# POIstick.net
KiCad netlist of a schematic drawn in EAGLE
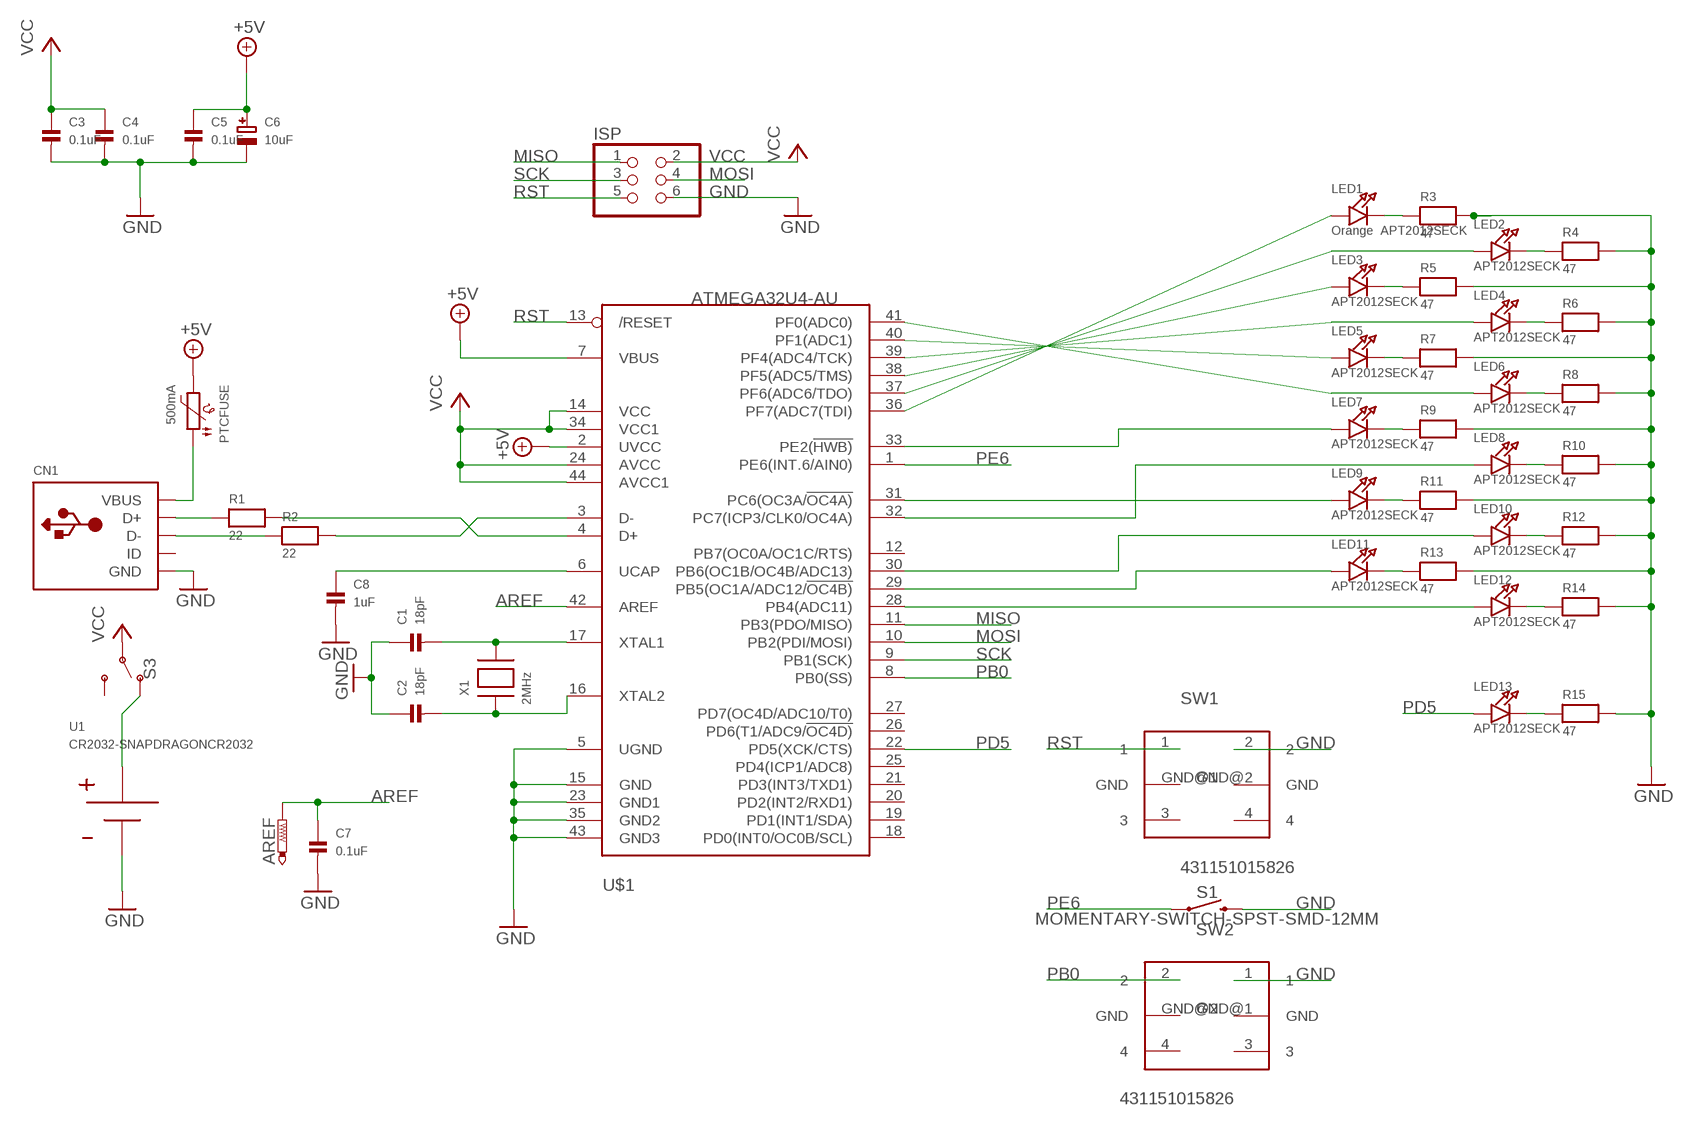
[diagram p0: schematic, sheet 1]

(export (version "E")
  (design (tool "Eeschema 10.0.6"))
  (components
    (comp (ref "AREF")
      (value "PTR1B1,27")
      (footprint "eagle-import:B1,27")
      (libsource (lib "eagle-import") (part "PTR1B1,27"))
    )
    (comp (ref "C1")
      (value "18pF")
      (footprint "eagle-import:0805")
      (libsource (lib "eagle-import") (part "CAP_CERAMIC0805"))
    )
    (comp (ref "C2")
      (value "18pF")
      (footprint "eagle-import:0805")
      (libsource (lib "eagle-import") (part "CAP_CERAMIC0805"))
    )
    (comp (ref "C3")
      (value "0.1uF")
      (footprint "eagle-import:0805")
      (libsource (lib "eagle-import") (part "CAP_CERAMIC0805"))
    )
    (comp (ref "C4")
      (value "0.1uF")
      (footprint "eagle-import:0805")
      (libsource (lib "eagle-import") (part "CAP_CERAMIC0805"))
    )
    (comp (ref "C5")
      (value "0.1uF")
      (footprint "eagle-import:0805")
      (libsource (lib "eagle-import") (part "CAP_CERAMIC0805"))
    )
    (comp (ref "C6")
      (value "10uF")
      (footprint "eagle-import:EIA3216-18_A-W")
      (libsource (lib "eagle-import") (part "CAP_TANTALUMA/3216_WAVE"))
    )
    (comp (ref "C7")
      (value "0.1uF")
      (footprint "eagle-import:0805")
      (libsource (lib "eagle-import") (part "CAP_CERAMIC0805"))
    )
    (comp (ref "C8")
      (value "1uF")
      (footprint "eagle-import:0805")
      (libsource (lib "eagle-import") (part "CAP_CERAMIC0805"))
    )
    (comp (ref "CN1")
      (value "USBMINIB")
      (footprint "eagle-import:USB-MINIB")
      (libsource (lib "eagle-import") (part "USBMINIB"))
    )
    (comp (ref "ISP")
      (value "PINHD-2X3")
      (footprint "eagle-import:2X03")
      (libsource (lib "eagle-import") (part "PINHD-2X3"))
    )
    (comp (ref "LED1")
      (value "Orange APT2012SECK")
      (footprint "eagle-import:CHIPLED_0805")
      (libsource (lib "eagle-import") (part "LED0805"))
    )
    (comp (ref "LED2")
      (value "APT2012SECK")
      (footprint "eagle-import:CHIPLED_0805")
      (libsource (lib "eagle-import") (part "LED0805"))
    )
    (comp (ref "LED3")
      (value "APT2012SECK")
      (footprint "eagle-import:CHIPLED_0805")
      (libsource (lib "eagle-import") (part "LED0805"))
    )
    (comp (ref "LED4")
      (value "APT2012SECK")
      (footprint "eagle-import:CHIPLED_0805")
      (libsource (lib "eagle-import") (part "LED0805"))
    )
    (comp (ref "LED5")
      (value "APT2012SECK")
      (footprint "eagle-import:CHIPLED_0805")
      (libsource (lib "eagle-import") (part "LED0805"))
    )
    (comp (ref "LED6")
      (value "APT2012SECK")
      (footprint "eagle-import:CHIPLED_0805")
      (libsource (lib "eagle-import") (part "LED0805"))
    )
    (comp (ref "LED7")
      (value "APT2012SECK")
      (footprint "eagle-import:CHIPLED_0805")
      (libsource (lib "eagle-import") (part "LED0805"))
    )
    (comp (ref "LED8")
      (value "APT2012SECK")
      (footprint "eagle-import:CHIPLED_0805")
      (libsource (lib "eagle-import") (part "LED0805"))
    )
    (comp (ref "LED9")
      (value "APT2012SECK")
      (footprint "eagle-import:CHIPLED_0805")
      (libsource (lib "eagle-import") (part "LED0805"))
    )
    (comp (ref "LED10")
      (value "APT2012SECK")
      (footprint "eagle-import:CHIPLED_0805")
      (libsource (lib "eagle-import") (part "LED0805"))
    )
    (comp (ref "LED11")
      (value "APT2012SECK")
      (footprint "eagle-import:CHIPLED_0805")
      (libsource (lib "eagle-import") (part "LED0805"))
    )
    (comp (ref "LED12")
      (value "APT2012SECK")
      (footprint "eagle-import:CHIPLED_0805")
      (libsource (lib "eagle-import") (part "LED0805"))
    )
    (comp (ref "LED13")
      (value "APT2012SECK")
      (footprint "eagle-import:CHIPLED_0805")
      (libsource (lib "eagle-import") (part "LED0805"))
    )
    (comp (ref "PTCFUSE")
      (value "500mA")
      (footprint "eagle-import:1206")
      (libsource (lib "eagle-import") (part "PTC1206"))
    )
    (comp (ref "R1")
      (value "22")
      (footprint "eagle-import:0805")
      (libsource (lib "eagle-import") (part "RESISTOR0805"))
    )
    (comp (ref "R2")
      (value "22")
      (footprint "eagle-import:0805")
      (libsource (lib "eagle-import") (part "RESISTOR0805"))
    )
    (comp (ref "R3")
      (value "47")
      (footprint "eagle-import:0805")
      (libsource (lib "eagle-import") (part "RESISTOR0805"))
    )
    (comp (ref "R4")
      (value "47")
      (footprint "eagle-import:0805")
      (libsource (lib "eagle-import") (part "RESISTOR0805"))
    )
    (comp (ref "R5")
      (value "47")
      (footprint "eagle-import:0805")
      (libsource (lib "eagle-import") (part "RESISTOR0805"))
    )
    (comp (ref "R6")
      (value "47")
      (footprint "eagle-import:0805")
      (libsource (lib "eagle-import") (part "RESISTOR0805"))
    )
    (comp (ref "R7")
      (value "47")
      (footprint "eagle-import:0805")
      (libsource (lib "eagle-import") (part "RESISTOR0805"))
    )
    (comp (ref "R8")
      (value "47")
      (footprint "eagle-import:0805")
      (libsource (lib "eagle-import") (part "RESISTOR0805"))
    )
    (comp (ref "R9")
      (value "47")
      (footprint "eagle-import:0805")
      (libsource (lib "eagle-import") (part "RESISTOR0805"))
    )
    (comp (ref "R10")
      (value "47")
      (footprint "eagle-import:0805")
      (libsource (lib "eagle-import") (part "RESISTOR0805"))
    )
    (comp (ref "R11")
      (value "47")
      (footprint "eagle-import:0805")
      (libsource (lib "eagle-import") (part "RESISTOR0805"))
    )
    (comp (ref "R12")
      (value "47")
      (footprint "eagle-import:0805")
      (libsource (lib "eagle-import") (part "RESISTOR0805"))
    )
    (comp (ref "R13")
      (value "47")
      (footprint "eagle-import:0805")
      (libsource (lib "eagle-import") (part "RESISTOR0805"))
    )
    (comp (ref "R14")
      (value "47")
      (footprint "eagle-import:0805")
      (libsource (lib "eagle-import") (part "RESISTOR0805"))
    )
    (comp (ref "R15")
      (value "47")
      (footprint "eagle-import:0805")
      (libsource (lib "eagle-import") (part "RESISTOR0805"))
    )
    (comp (ref "S1")
      (value "MOMENTARY-SWITCH-SPST-SMD-12MM")
      (footprint "eagle-import:TACTILE_SWITCH_SMD_12MM")
      (libsource (lib "eagle-import") (part "MOMENTARY-SWITCH-SPST-SMD-12MM"))
    )
    (comp (ref "S3")
      (value "SWITCH-SPDT-SMD-RIGHT-ANGLE")
      (footprint "eagle-import:SWITCH_SPST_SMD_A")
      (libsource (lib "eagle-import") (part "SWITCH-SPDT-SMD-RIGHT-ANGLE"))
    )
    (comp (ref "SW1")
      (value "431151015826")
      (footprint "eagle-import:431181015816")
      (libsource (lib "eagle-import") (part "431151015826"))
    )
    (comp (ref "SW2")
      (value "431151015826")
      (footprint "eagle-import:431181015816")
      (libsource (lib "eagle-import") (part "431151015826"))
    )
    (comp (ref "U$1")
      (value "ATMEGA32U4-AU")
      (footprint "eagle-import:TQFP44")
      (libsource (lib "eagle-import") (part "ATMEGA32U4-AU"))
    )
    (comp (ref "U1")
      (value "CR2032-SNAPDRAGONCR2032")
      (footprint "eagle-import:CR2032-SNAPDRAGON")
      (libsource (lib "eagle-import") (part "CR2032-SNAPDRAGONCR2032"))
    )
    (comp (ref "X1")
      (value "2MHz")
      (footprint "eagle-import:NX5032")
      (libsource (lib "eagle-import") (part "XTALNX5032"))
    )
  )
  (nets
    (net (code "1") (name "+5V") (class "Default")
      (node (ref "C5") (pin "1") (pinfunction "P$1_1") (pintype "passive"))
      (node (ref "C6") (pin "+") (pinfunction "+_+") (pintype "passive"))
      (node (ref "PTCFUSE") (pin "2") (pinfunction "2_2") (pintype "passive"))
      (node (ref "U$1") (pin "2") (pinfunction "UVCC_2") (pintype "bidirectional"))
      (node (ref "U$1") (pin "7") (pinfunction "VBUS_7") (pintype "bidirectional"))
    )
    (net (code "2") (name "/AREF") (class "Default")
      (node (ref "AREF") (pin "TP") (pinfunction "TP_TP") (pintype "input"))
      (node (ref "C7") (pin "1") (pinfunction "P$1_1") (pintype "passive"))
      (node (ref "U$1") (pin "42") (pinfunction "AREF_42") (pintype "bidirectional"))
    )
    (net (code "3") (name "/MISO") (class "Default")
      (node (ref "ISP") (pin "1") (pinfunction "1_1") (pintype "passive"))
      (node (ref "U$1") (pin "11") (pinfunction "PB3(PDO/MISO)_11") (pintype "bidirectional"))
    )
    (net (code "4") (name "/MOSI") (class "Default")
      (node (ref "ISP") (pin "4") (pinfunction "4_4") (pintype "passive"))
      (node (ref "U$1") (pin "10") (pinfunction "PB2(PDI/MOSI)_10") (pintype "bidirectional"))
    )
    (net (code "5") (name "/PB0") (class "Default")
      (node (ref "SW2") (pin "2") (pinfunction "2_2") (pintype "bidirectional"))
      (node (ref "U$1") (pin "8") (pinfunction "PB0(SS)_8") (pintype "bidirectional"))
    )
    (net (code "6") (name "/PD5") (class "Default")
      (node (ref "LED13") (pin "A") (pinfunction "A_A") (pintype "passive"))
      (node (ref "U$1") (pin "22") (pinfunction "PD5(XCK/CTS)_22") (pintype "bidirectional"))
    )
    (net (code "7") (name "/PE6") (class "Default")
      (node (ref "S1") (pin "1") (pinfunction "1_1") (pintype "passive"))
      (node (ref "U$1") (pin "1") (pinfunction "PE6(INT.6/AIN0)_1") (pintype "bidirectional"))
    )
    (net (code "8") (name "/RST") (class "Default")
      (node (ref "ISP") (pin "5") (pinfunction "5_5") (pintype "passive"))
      (node (ref "SW1") (pin "1") (pinfunction "1_1") (pintype "bidirectional"))
      (node (ref "U$1") (pin "13") (pinfunction "/RESET_13") (pintype "bidirectional"))
    )
    (net (code "9") (name "/SCK") (class "Default")
      (node (ref "ISP") (pin "3") (pinfunction "3_3") (pintype "passive"))
      (node (ref "U$1") (pin "9") (pinfunction "PB1(SCK)_9") (pintype "bidirectional"))
    )
    (net (code "10") (name "GND") (class "Default")
      (node (ref "C1") (pin "1") (pinfunction "P$1_1") (pintype "passive"))
      (node (ref "C2") (pin "1") (pinfunction "P$1_1") (pintype "passive"))
      (node (ref "C3") (pin "2") (pinfunction "P$2_2") (pintype "passive"))
      (node (ref "C4") (pin "2") (pinfunction "P$2_2") (pintype "passive"))
      (node (ref "C5") (pin "2") (pinfunction "P$2_2") (pintype "passive"))
      (node (ref "C6") (pin "-") (pinfunction "-_-") (pintype "passive"))
      (node (ref "C7") (pin "2") (pinfunction "P$2_2") (pintype "passive"))
      (node (ref "C8") (pin "2") (pinfunction "P$2_2") (pintype "passive"))
      (node (ref "CN1") (pin "GND") (pinfunction "GND_GND") (pintype "power_in"))
      (node (ref "ISP") (pin "6") (pinfunction "6_6") (pintype "passive"))
      (node (ref "R10") (pin "2") (pinfunction "2_2") (pintype "passive"))
      (node (ref "R11") (pin "2") (pinfunction "2_2") (pintype "passive"))
      (node (ref "R12") (pin "2") (pinfunction "2_2") (pintype "passive"))
      (node (ref "R13") (pin "2") (pinfunction "2_2") (pintype "passive"))
      (node (ref "R14") (pin "2") (pinfunction "2_2") (pintype "passive"))
      (node (ref "R15") (pin "2") (pinfunction "2_2") (pintype "passive"))
      (node (ref "R3") (pin "2") (pinfunction "2_2") (pintype "passive"))
      (node (ref "R4") (pin "2") (pinfunction "2_2") (pintype "passive"))
      (node (ref "R5") (pin "2") (pinfunction "2_2") (pintype "passive"))
      (node (ref "R6") (pin "2") (pinfunction "2_2") (pintype "passive"))
      (node (ref "R7") (pin "2") (pinfunction "2_2") (pintype "passive"))
      (node (ref "R8") (pin "2") (pinfunction "2_2") (pintype "passive"))
      (node (ref "R9") (pin "2") (pinfunction "2_2") (pintype "passive"))
      (node (ref "S1") (pin "3") (pinfunction "2_3") (pintype "passive"))
      (node (ref "SW1") (pin "2") (pinfunction "2_2") (pintype "bidirectional"))
      (node (ref "SW2") (pin "1") (pinfunction "1_1") (pintype "bidirectional"))
      (node (ref "U$1") (pin "15") (pinfunction "GND_15") (pintype "bidirectional"))
      (node (ref "U$1") (pin "23") (pinfunction "GND1_23") (pintype "bidirectional"))
      (node (ref "U$1") (pin "35") (pinfunction "GND2_35") (pintype "bidirectional"))
      (node (ref "U$1") (pin "43") (pinfunction "GND3_43") (pintype "bidirectional"))
      (node (ref "U$1") (pin "5") (pinfunction "UGND_5") (pintype "bidirectional"))
      (node (ref "U1") (pin "V-") (pinfunction "V-_V-") (pintype "bidirectional"))
    )
    (net (code "11") (name "Net-(C1-P$2)") (class "Default")
      (node (ref "C1") (pin "2") (pinfunction "P$2_2") (pintype "passive"))
      (node (ref "U$1") (pin "17") (pinfunction "XTAL1_17") (pintype "bidirectional"))
      (node (ref "X1") (pin "P$2") (pinfunction "P$2_P$2") (pintype "bidirectional"))
    )
    (net (code "12") (name "Net-(C2-P$2)") (class "Default")
      (node (ref "C2") (pin "2") (pinfunction "P$2_2") (pintype "passive"))
      (node (ref "U$1") (pin "16") (pinfunction "XTAL2_16") (pintype "bidirectional"))
      (node (ref "X1") (pin "P$1") (pinfunction "P$1_P$1") (pintype "bidirectional"))
    )
    (net (code "13") (name "Net-(C8-P$1)") (class "Default")
      (node (ref "C8") (pin "1") (pinfunction "P$1_1") (pintype "passive"))
      (node (ref "U$1") (pin "6") (pinfunction "UCAP_6") (pintype "bidirectional"))
    )
    (net (code "14") (name "Net-(CN1-PadD+)") (class "Default")
      (node (ref "CN1") (pin "D+") (pinfunction "D+_D+") (pintype "bidirectional"))
      (node (ref "R1") (pin "1") (pinfunction "1_1") (pintype "passive"))
    )
    (net (code "15") (name "Net-(CN1-PadD-)") (class "Default")
      (node (ref "CN1") (pin "D-") (pinfunction "D-_D-") (pintype "bidirectional"))
      (node (ref "R2") (pin "1") (pinfunction "1_1") (pintype "passive"))
    )
    (net (code "16") (name "Net-(CN1-PadVBUS)") (class "Default")
      (node (ref "CN1") (pin "VBUS") (pinfunction "VBUS_VBUS") (pintype "power_in"))
      (node (ref "PTCFUSE") (pin "1") (pinfunction "1_1") (pintype "passive"))
    )
    (net (code "17") (name "Net-(LED1-PadC)") (class "Default")
      (node (ref "LED1") (pin "C") (pinfunction "C_C") (pintype "passive"))
      (node (ref "R3") (pin "1") (pinfunction "1_1") (pintype "passive"))
    )
    (net (code "18") (name "Net-(LED2-PadC)") (class "Default")
      (node (ref "LED2") (pin "C") (pinfunction "C_C") (pintype "passive"))
      (node (ref "R4") (pin "1") (pinfunction "1_1") (pintype "passive"))
    )
    (net (code "19") (name "Net-(LED3-PadC)") (class "Default")
      (node (ref "LED3") (pin "C") (pinfunction "C_C") (pintype "passive"))
      (node (ref "R5") (pin "1") (pinfunction "1_1") (pintype "passive"))
    )
    (net (code "20") (name "Net-(LED4-PadC)") (class "Default")
      (node (ref "LED4") (pin "C") (pinfunction "C_C") (pintype "passive"))
      (node (ref "R6") (pin "1") (pinfunction "1_1") (pintype "passive"))
    )
    (net (code "21") (name "Net-(LED5-PadC)") (class "Default")
      (node (ref "LED5") (pin "C") (pinfunction "C_C") (pintype "passive"))
      (node (ref "R7") (pin "1") (pinfunction "1_1") (pintype "passive"))
    )
    (net (code "22") (name "Net-(LED6-PadC)") (class "Default")
      (node (ref "LED6") (pin "C") (pinfunction "C_C") (pintype "passive"))
      (node (ref "R8") (pin "1") (pinfunction "1_1") (pintype "passive"))
    )
    (net (code "23") (name "Net-(LED7-PadC)") (class "Default")
      (node (ref "LED7") (pin "C") (pinfunction "C_C") (pintype "passive"))
      (node (ref "R9") (pin "1") (pinfunction "1_1") (pintype "passive"))
    )
    (net (code "24") (name "Net-(LED8-PadC)") (class "Default")
      (node (ref "LED8") (pin "C") (pinfunction "C_C") (pintype "passive"))
      (node (ref "R10") (pin "1") (pinfunction "1_1") (pintype "passive"))
    )
    (net (code "25") (name "Net-(LED9-PadC)") (class "Default")
      (node (ref "LED9") (pin "C") (pinfunction "C_C") (pintype "passive"))
      (node (ref "R11") (pin "1") (pinfunction "1_1") (pintype "passive"))
    )
    (net (code "26") (name "Net-(LED10-PadC)") (class "Default")
      (node (ref "LED10") (pin "C") (pinfunction "C_C") (pintype "passive"))
      (node (ref "R12") (pin "1") (pinfunction "1_1") (pintype "passive"))
    )
    (net (code "27") (name "Net-(LED11-PadC)") (class "Default")
      (node (ref "LED11") (pin "C") (pinfunction "C_C") (pintype "passive"))
      (node (ref "R13") (pin "1") (pinfunction "1_1") (pintype "passive"))
    )
    (net (code "28") (name "Net-(LED12-PadC)") (class "Default")
      (node (ref "LED12") (pin "C") (pinfunction "C_C") (pintype "passive"))
      (node (ref "R14") (pin "1") (pinfunction "1_1") (pintype "passive"))
    )
    (net (code "29") (name "Net-(LED13-PadC)") (class "Default")
      (node (ref "LED13") (pin "C") (pinfunction "C_C") (pintype "passive"))
      (node (ref "R15") (pin "1") (pinfunction "1_1") (pintype "passive"))
    )
    (net (code "30") (name "Net-(S3-O)") (class "Default")
      (node (ref "S3") (pin "1") (pinfunction "O_1") (pintype "passive"))
      (node (ref "U1") (pin "V+") (pinfunction "V+_V+") (pintype "passive"))
    )
    (net (code "31") (name "Net-(U$1-D+)") (class "Default")
      (node (ref "R1") (pin "2") (pinfunction "2_2") (pintype "passive"))
      (node (ref "U$1") (pin "4") (pinfunction "D+_4") (pintype "bidirectional"))
    )
    (net (code "32") (name "Net-(U$1-D-)") (class "Default")
      (node (ref "R2") (pin "2") (pinfunction "2_2") (pintype "passive"))
      (node (ref "U$1") (pin "3") (pinfunction "D-_3") (pintype "bidirectional"))
    )
    (net (code "33") (name "Net-(U$1-PB4(ADC11))") (class "Default")
      (node (ref "LED12") (pin "A") (pinfunction "A_A") (pintype "passive"))
      (node (ref "U$1") (pin "28") (pinfunction "PB4(ADC11)_28") (pintype "bidirectional"))
    )
    (net (code "34") (name "Net-(U$1-PB5(OC1A{slash}ADC12{slash}~{OC4B}))") (class "Default")
      (node (ref "LED11") (pin "A") (pinfunction "A_A") (pintype "passive"))
      (node (ref "U$1") (pin "29") (pinfunction "PB5(OC1A/ADC12/~{OC4B})_29") (pintype "bidirectional"))
    )
    (net (code "35") (name "Net-(U$1-PB6(OC1B{slash}OC4B{slash}ADC13))") (class "Default")
      (node (ref "LED10") (pin "A") (pinfunction "A_A") (pintype "passive"))
      (node (ref "U$1") (pin "30") (pinfunction "PB6(OC1B/OC4B/ADC13)_30") (pintype "bidirectional"))
    )
    (net (code "36") (name "Net-(U$1-PC6(OC3A{slash}~{OC4A}))") (class "Default")
      (node (ref "LED9") (pin "A") (pinfunction "A_A") (pintype "passive"))
      (node (ref "U$1") (pin "31") (pinfunction "PC6(OC3A/~{OC4A})_31") (pintype "bidirectional"))
    )
    (net (code "37") (name "Net-(U$1-PC7(ICP3{slash}CLK0{slash}OC4A))") (class "Default")
      (node (ref "LED8") (pin "A") (pinfunction "A_A") (pintype "passive"))
      (node (ref "U$1") (pin "32") (pinfunction "PC7(ICP3/CLK0/OC4A)_32") (pintype "bidirectional"))
    )
    (net (code "38") (name "Net-(U$1-PE2(~{HWB}))") (class "Default")
      (node (ref "LED7") (pin "A") (pinfunction "A_A") (pintype "passive"))
      (node (ref "U$1") (pin "33") (pinfunction "PE2(~{HWB})_33") (pintype "bidirectional"))
    )
    (net (code "39") (name "Net-(U$1-PF0(ADC0))") (class "Default")
      (node (ref "LED6") (pin "A") (pinfunction "A_A") (pintype "passive"))
      (node (ref "U$1") (pin "41") (pinfunction "PF0(ADC0)_41") (pintype "bidirectional"))
    )
    (net (code "40") (name "Net-(U$1-PF1(ADC1))") (class "Default")
      (node (ref "LED5") (pin "A") (pinfunction "A_A") (pintype "passive"))
      (node (ref "U$1") (pin "40") (pinfunction "PF1(ADC1)_40") (pintype "bidirectional"))
    )
    (net (code "41") (name "Net-(U$1-PF4(ADC4{slash}TCK))") (class "Default")
      (node (ref "LED4") (pin "A") (pinfunction "A_A") (pintype "passive"))
      (node (ref "U$1") (pin "39") (pinfunction "PF4(ADC4/TCK)_39") (pintype "bidirectional"))
    )
    (net (code "42") (name "Net-(U$1-PF5(ADC5{slash}TMS))") (class "Default")
      (node (ref "LED3") (pin "A") (pinfunction "A_A") (pintype "passive"))
      (node (ref "U$1") (pin "38") (pinfunction "PF5(ADC5/TMS)_38") (pintype "bidirectional"))
    )
    (net (code "43") (name "Net-(U$1-PF6(ADC6{slash}TDO))") (class "Default")
      (node (ref "LED2") (pin "A") (pinfunction "A_A") (pintype "passive"))
      (node (ref "U$1") (pin "37") (pinfunction "PF6(ADC6/TDO)_37") (pintype "bidirectional"))
    )
    (net (code "44") (name "Net-(U$1-PF7(ADC7(TDI))") (class "Default")
      (node (ref "LED1") (pin "A") (pinfunction "A_A") (pintype "passive"))
      (node (ref "U$1") (pin "36") (pinfunction "PF7(ADC7(TDI)_36") (pintype "bidirectional"))
    )
    (net (code "45") (name "VCC") (class "Default")
      (node (ref "C3") (pin "1") (pinfunction "P$1_1") (pintype "passive"))
      (node (ref "C4") (pin "1") (pinfunction "P$1_1") (pintype "passive"))
      (node (ref "ISP") (pin "2") (pinfunction "2_2") (pintype "passive"))
      (node (ref "S3") (pin "2") (pinfunction "P_2") (pintype "passive"))
      (node (ref "U$1") (pin "14") (pinfunction "VCC_14") (pintype "bidirectional"))
      (node (ref "U$1") (pin "24") (pinfunction "AVCC_24") (pintype "bidirectional"))
      (node (ref "U$1") (pin "34") (pinfunction "VCC1_34") (pintype "bidirectional"))
      (node (ref "U$1") (pin "44") (pinfunction "AVCC1_44") (pintype "bidirectional"))
    )
    (net (code "46") (name "unconnected-(CN1-PadID)") (class "Default")
      (node (ref "CN1") (pin "ID") (pinfunction "ID_ID") (pintype "bidirectional"))
    )
    (net (code "47") (name "unconnected-(S3-S-Pad3)") (class "Default")
      (node (ref "S3") (pin "3") (pinfunction "S_3") (pintype "passive"))
    )
    (net (code "48") (name "unconnected-(SW1-GND-PadGND@1)") (class "Default")
      (node (ref "SW1") (pin "GND@1") (pinfunction "GND_GND@1") (pintype "bidirectional"))
    )
    (net (code "49") (name "unconnected-(SW1-GND-PadGND@2)") (class "Default")
      (node (ref "SW1") (pin "GND@2") (pinfunction "GND_GND@2") (pintype "bidirectional"))
    )
    (net (code "50") (name "unconnected-(SW1-Pad3)") (class "Default")
      (node (ref "SW1") (pin "3") (pinfunction "3_3") (pintype "bidirectional"))
    )
    (net (code "51") (name "unconnected-(SW1-Pad4)") (class "Default")
      (node (ref "SW1") (pin "4") (pinfunction "4_4") (pintype "bidirectional"))
    )
    (net (code "52") (name "unconnected-(SW2-GND-PadGND@1)") (class "Default")
      (node (ref "SW2") (pin "GND@1") (pinfunction "GND_GND@1") (pintype "bidirectional"))
    )
    (net (code "53") (name "unconnected-(SW2-GND-PadGND@2)") (class "Default")
      (node (ref "SW2") (pin "GND@2") (pinfunction "GND_GND@2") (pintype "bidirectional"))
    )
    (net (code "54") (name "unconnected-(SW2-Pad3)") (class "Default")
      (node (ref "SW2") (pin "3") (pinfunction "3_3") (pintype "bidirectional"))
    )
    (net (code "55") (name "unconnected-(SW2-Pad4)") (class "Default")
      (node (ref "SW2") (pin "4") (pinfunction "4_4") (pintype "bidirectional"))
    )
    (net (code "56") (name "unconnected-(U$1-PB7(OC0A{slash}OC1C{slash}RTS)-Pad12)") (class "Default")
      (node (ref "U$1") (pin "12") (pinfunction "PB7(OC0A/OC1C/RTS)_12") (pintype "bidirectional"))
    )
    (net (code "57") (name "unconnected-(U$1-PD0(INT0{slash}OC0B{slash}SCL)-Pad18)") (class "Default")
      (node (ref "U$1") (pin "18") (pinfunction "PD0(INT0/OC0B/SCL)_18") (pintype "bidirectional"))
    )
    (net (code "58") (name "unconnected-(U$1-PD1(INT1{slash}SDA)-Pad19)") (class "Default")
      (node (ref "U$1") (pin "19") (pinfunction "PD1(INT1/SDA)_19") (pintype "bidirectional"))
    )
    (net (code "59") (name "unconnected-(U$1-PD2(INT2{slash}RXD1)-Pad20)") (class "Default")
      (node (ref "U$1") (pin "20") (pinfunction "PD2(INT2/RXD1)_20") (pintype "bidirectional"))
    )
    (net (code "60") (name "unconnected-(U$1-PD3(INT3{slash}TXD1)-Pad21)") (class "Default")
      (node (ref "U$1") (pin "21") (pinfunction "PD3(INT3/TXD1)_21") (pintype "bidirectional"))
    )
    (net (code "61") (name "unconnected-(U$1-PD4(ICP1{slash}ADC8)-Pad25)") (class "Default")
      (node (ref "U$1") (pin "25") (pinfunction "PD4(ICP1/ADC8)_25") (pintype "bidirectional"))
    )
    (net (code "62") (name "unconnected-(U$1-PD6(T1{slash}ADC9{slash}~{OC4D})-Pad26)") (class "Default")
      (node (ref "U$1") (pin "26") (pinfunction "PD6(T1/ADC9/~{OC4D})_26") (pintype "bidirectional"))
    )
    (net (code "63") (name "unconnected-(U$1-PD7(OC4D{slash}ADC10{slash}T0)-Pad27)") (class "Default")
      (node (ref "U$1") (pin "27") (pinfunction "PD7(OC4D/ADC10/T0)_27") (pintype "bidirectional"))
    )
  )
)
